# devboard_kw2xd_v2_0.net
KiCad netlist of a schematic drawn in EAGLE
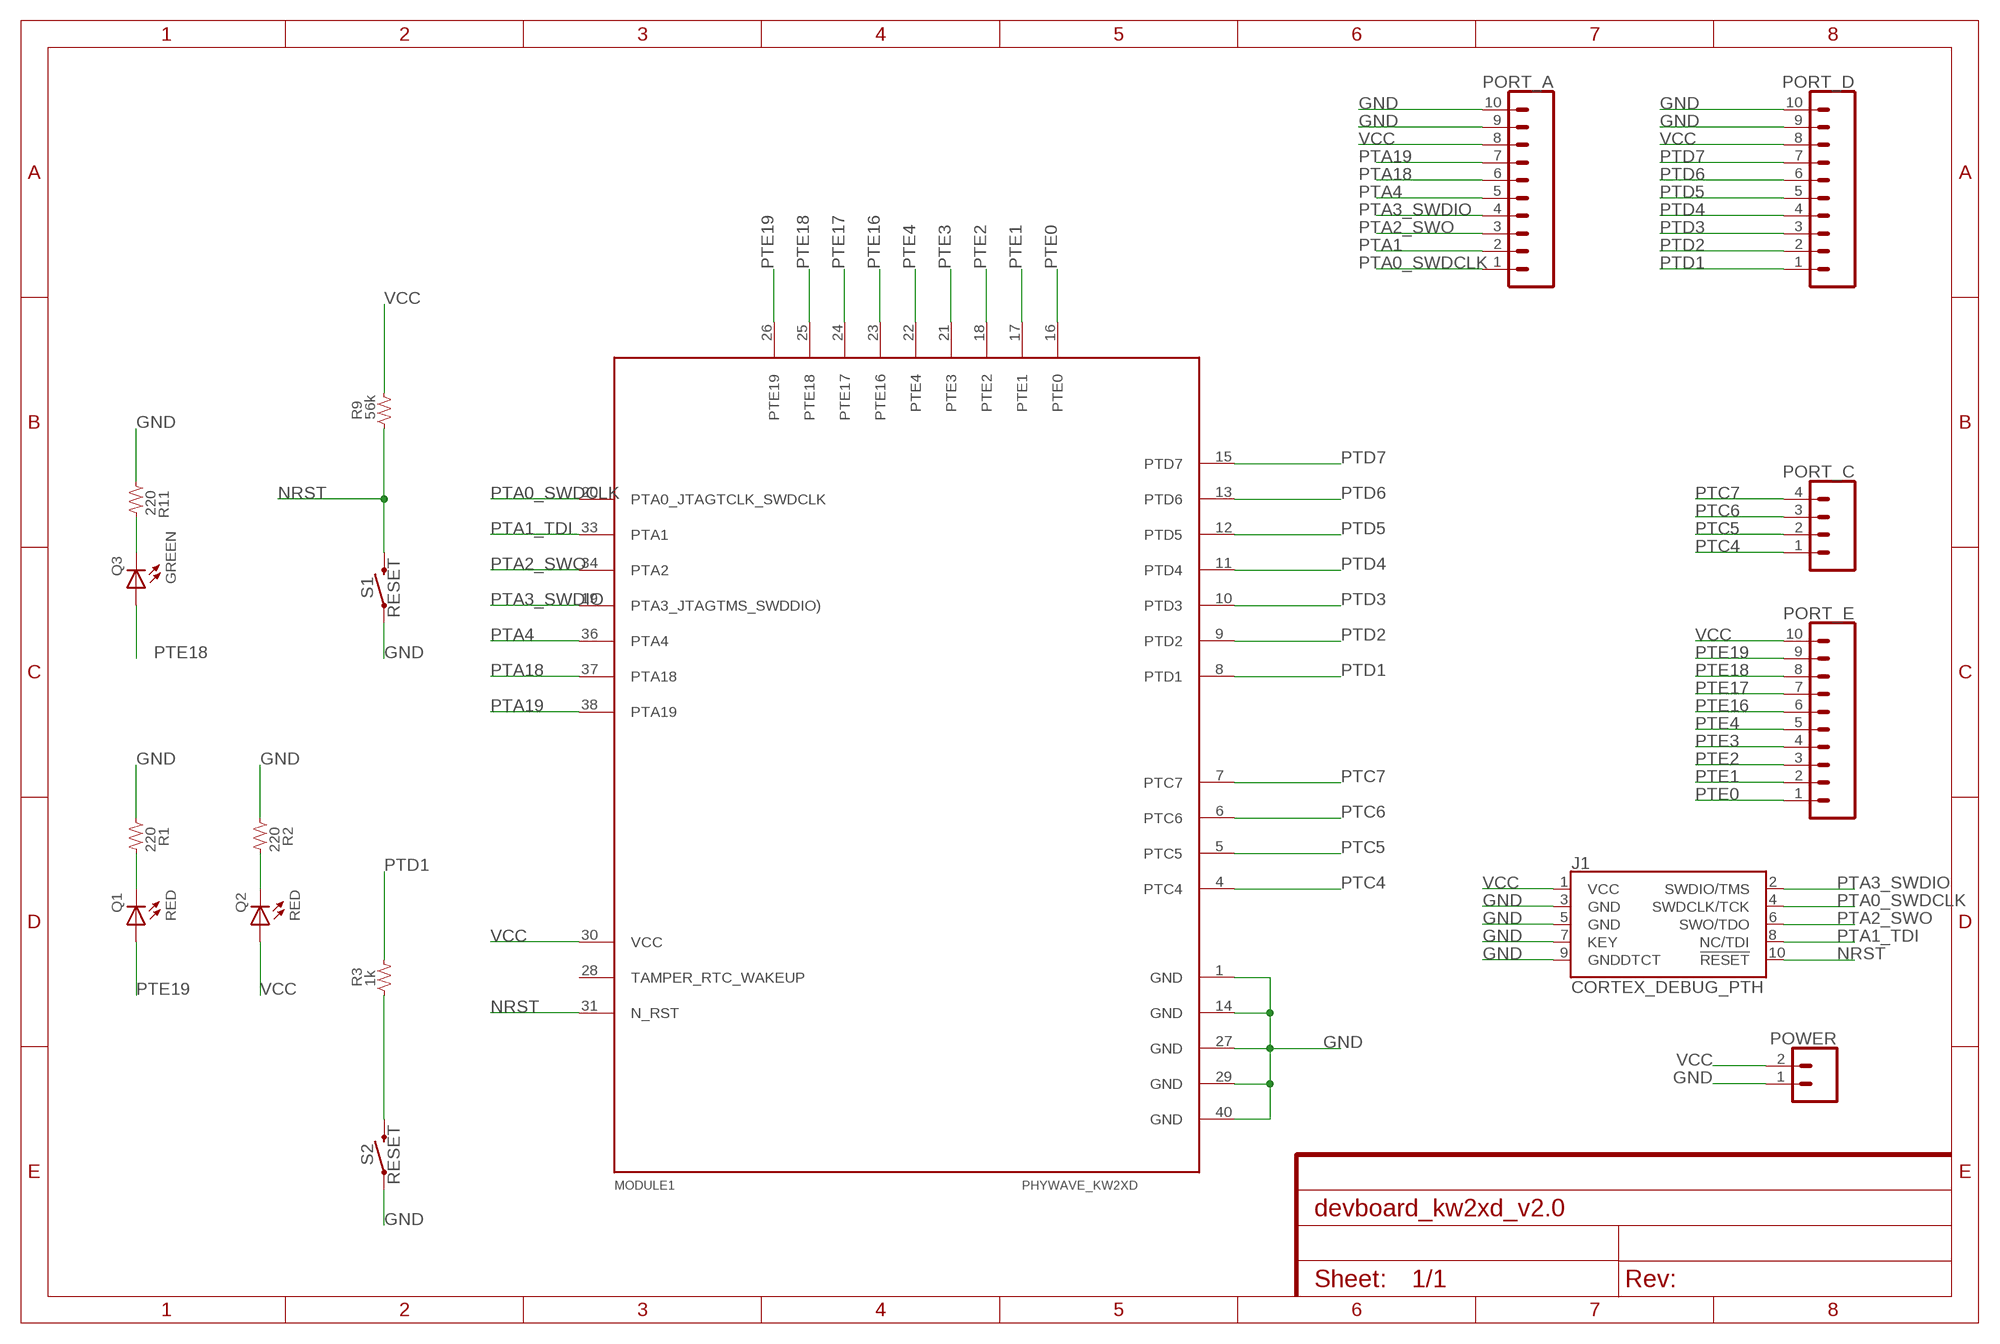
[diagram p0: schematic, sheet 1]

(export (version "E")
  (design (tool "Eeschema 10.0.6"))
  (components
    (comp (ref "J1")
      (value "CORTEX_DEBUG_PTH")
      (footprint "eagle-import:2X5-PTH-1.27MM")
      (libsource (lib "eagle-import") (part "CORTEX_DEBUG_PTH"))
    )
    (comp (ref "MODULE1")
      (value "PHYWAVE_KW2XD")
      (footprint "eagle-import:PHYWAVE_KW2XD")
      (libsource (lib "eagle-import") (part "PHYWAVE_KW2XD"))
    )
    (comp (ref "PORT_A")
      (value "CONN_10\"")
      (footprint "eagle-import:1X10")
      (libsource (lib "eagle-import") (part "CONN_10{dblquote}"))
    )
    (comp (ref "PORT_C")
      (value "CONN_04")
      (footprint "eagle-import:1X04")
      (libsource (lib "eagle-import") (part "CONN_04"))
    )
    (comp (ref "PORT_D")
      (value "CONN_10\"")
      (footprint "eagle-import:1X10")
      (libsource (lib "eagle-import") (part "CONN_10{dblquote}"))
    )
    (comp (ref "PORT_E")
      (value "CONN_10\"")
      (footprint "eagle-import:1X10")
      (libsource (lib "eagle-import") (part "CONN_10{dblquote}"))
    )
    (comp (ref "POWER")
      (value "CONN_02")
      (footprint "eagle-import:1X02")
      (libsource (lib "eagle-import") (part "CONN_02"))
    )
    (comp (ref "Q1")
      (value "RED")
      (footprint "eagle-import:LED0603")
      (libsource (lib "eagle-import") (part "LED-0603"))
    )
    (comp (ref "Q2")
      (value "RED")
      (footprint "eagle-import:LED0603")
      (libsource (lib "eagle-import") (part "LED-0603"))
    )
    (comp (ref "Q3")
      (value "GREEN")
      (footprint "eagle-import:LED0603")
      (libsource (lib "eagle-import") (part "LED-0603"))
    )
    (comp (ref "R1")
      (value "220")
      (footprint "eagle-import:SMD0603")
      (libsource (lib "eagle-import") (part "R-0603"))
    )
    (comp (ref "R2")
      (value "220")
      (footprint "eagle-import:SMD0603")
      (libsource (lib "eagle-import") (part "R-0603"))
    )
    (comp (ref "R3")
      (value "1k")
      (footprint "eagle-import:SMD0603")
      (libsource (lib "eagle-import") (part "R-0603"))
    )
    (comp (ref "R9")
      (value "56k")
      (footprint "eagle-import:SMD0603")
      (libsource (lib "eagle-import") (part "R-0603"))
    )
    (comp (ref "R11")
      (value "220")
      (footprint "eagle-import:SMD0603")
      (libsource (lib "eagle-import") (part "R-0603"))
    )
    (comp (ref "S1")
      (value "RESET")
      (footprint "eagle-import:TACTILE_SWITCH_SMD_4.6X2.8MM")
      (libsource (lib "eagle-import") (part "MOMENTARY-SWITCH-SPST-SMD-4.6X2.8MM"))
    )
    (comp (ref "S2")
      (value "RESET")
      (footprint "eagle-import:TACTILE_SWITCH_SMD_4.6X2.8MM")
      (libsource (lib "eagle-import") (part "MOMENTARY-SWITCH-SPST-SMD-4.6X2.8MM"))
    )
  )
  (nets
    (net (code "1") (name "/GND") (class "Default")
      (node (ref "J1") (pin "3") (pinfunction "GND_3") (pintype "bidirectional"))
      (node (ref "J1") (pin "5") (pinfunction "GND_5") (pintype "bidirectional"))
      (node (ref "J1") (pin "7") (pinfunction "KEY_7") (pintype "bidirectional"))
      (node (ref "J1") (pin "9") (pinfunction "GNDDTCT_9") (pintype "bidirectional"))
      (node (ref "MODULE1") (pin "1") (pinfunction "GND_1") (pintype "bidirectional"))
      (node (ref "MODULE1") (pin "14") (pinfunction "GND_14") (pintype "bidirectional"))
      (node (ref "MODULE1") (pin "27") (pinfunction "GND_27") (pintype "bidirectional"))
      (node (ref "MODULE1") (pin "29") (pinfunction "GND_29") (pintype "bidirectional"))
      (node (ref "MODULE1") (pin "40") (pinfunction "GND_40") (pintype "bidirectional"))
      (node (ref "PORT_A") (pin "10") (pinfunction "10_10") (pintype "passive"))
      (node (ref "PORT_A") (pin "9") (pinfunction "9_9") (pintype "passive"))
      (node (ref "PORT_D") (pin "10") (pinfunction "10_10") (pintype "passive"))
      (node (ref "PORT_D") (pin "9") (pinfunction "9_9") (pintype "passive"))
      (node (ref "POWER") (pin "1") (pinfunction "1_1") (pintype "passive"))
      (node (ref "R1") (pin "1") (pinfunction "1_1") (pintype "passive"))
      (node (ref "R11") (pin "1") (pinfunction "1_1") (pintype "passive"))
      (node (ref "R2") (pin "1") (pinfunction "1_1") (pintype "passive"))
      (node (ref "S1") (pin "1") (pinfunction "1_1") (pintype "passive"))
      (node (ref "S1") (pin "2") (pinfunction "1_2") (pintype "passive"))
      (node (ref "S2") (pin "1") (pinfunction "1_1") (pintype "passive"))
      (node (ref "S2") (pin "2") (pinfunction "1_2") (pintype "passive"))
    )
    (net (code "2") (name "/NRST") (class "Default")
      (node (ref "J1") (pin "10") (pinfunction "~{RESET}_10") (pintype "bidirectional"))
      (node (ref "MODULE1") (pin "31") (pinfunction "N_RST_31") (pintype "bidirectional"))
      (node (ref "R3") (pin "1") (pinfunction "1_1") (pintype "passive"))
      (node (ref "R9") (pin "1") (pinfunction "1_1") (pintype "passive"))
      (node (ref "S1") (pin "3") (pinfunction "2_3") (pintype "passive"))
      (node (ref "S1") (pin "4") (pinfunction "2_4") (pintype "passive"))
      (node (ref "S2") (pin "3") (pinfunction "2_3") (pintype "passive"))
      (node (ref "S2") (pin "4") (pinfunction "2_4") (pintype "passive"))
    )
    (net (code "3") (name "/PTA0_SWDCLK") (class "Default")
      (node (ref "J1") (pin "4") (pinfunction "SWDCLK/TCK_4") (pintype "bidirectional"))
      (node (ref "MODULE1") (pin "20") (pinfunction "PTA0_JTAGTCLK_SWDCLK_20") (pintype "bidirectional"))
      (node (ref "PORT_A") (pin "1") (pinfunction "1_1") (pintype "passive"))
    )
    (net (code "4") (name "/PTA1") (class "Default")
      (node (ref "PORT_A") (pin "2") (pinfunction "2_2") (pintype "passive"))
    )
    (net (code "5") (name "/PTA1_TDI") (class "Default")
      (node (ref "J1") (pin "8") (pinfunction "NC/TDI_8") (pintype "bidirectional"))
      (node (ref "MODULE1") (pin "33") (pinfunction "PTA1_33") (pintype "bidirectional"))
    )
    (net (code "6") (name "/PTA2_SWO") (class "Default")
      (node (ref "J1") (pin "6") (pinfunction "SWO/TDO_6") (pintype "bidirectional"))
      (node (ref "MODULE1") (pin "34") (pinfunction "PTA2_34") (pintype "bidirectional"))
      (node (ref "PORT_A") (pin "3") (pinfunction "3_3") (pintype "passive"))
    )
    (net (code "7") (name "/PTA3_SWDIO") (class "Default")
      (node (ref "J1") (pin "2") (pinfunction "SWDIO/TMS_2") (pintype "bidirectional"))
      (node (ref "MODULE1") (pin "19") (pinfunction "PTA3_JTAGTMS_SWDDIO)_19") (pintype "bidirectional"))
      (node (ref "PORT_A") (pin "4") (pinfunction "4_4") (pintype "passive"))
    )
    (net (code "8") (name "/PTA4") (class "Default")
      (node (ref "MODULE1") (pin "36") (pinfunction "PTA4_36") (pintype "bidirectional"))
      (node (ref "PORT_A") (pin "5") (pinfunction "5_5") (pintype "passive"))
    )
    (net (code "9") (name "/PTA18") (class "Default")
      (node (ref "MODULE1") (pin "37") (pinfunction "PTA18_37") (pintype "bidirectional"))
      (node (ref "PORT_A") (pin "6") (pinfunction "6_6") (pintype "passive"))
    )
    (net (code "10") (name "/PTA19") (class "Default")
      (node (ref "MODULE1") (pin "38") (pinfunction "PTA19_38") (pintype "bidirectional"))
      (node (ref "PORT_A") (pin "7") (pinfunction "7_7") (pintype "passive"))
    )
    (net (code "11") (name "/PTC4") (class "Default")
      (node (ref "MODULE1") (pin "4") (pinfunction "PTC4_4") (pintype "bidirectional"))
      (node (ref "PORT_C") (pin "1") (pinfunction "1_1") (pintype "passive"))
    )
    (net (code "12") (name "/PTC5") (class "Default")
      (node (ref "MODULE1") (pin "5") (pinfunction "PTC5_5") (pintype "bidirectional"))
      (node (ref "PORT_C") (pin "2") (pinfunction "2_2") (pintype "passive"))
    )
    (net (code "13") (name "/PTC6") (class "Default")
      (node (ref "MODULE1") (pin "6") (pinfunction "PTC6_6") (pintype "bidirectional"))
      (node (ref "PORT_C") (pin "3") (pinfunction "3_3") (pintype "passive"))
    )
    (net (code "14") (name "/PTC7") (class "Default")
      (node (ref "MODULE1") (pin "7") (pinfunction "PTC7_7") (pintype "bidirectional"))
      (node (ref "PORT_C") (pin "4") (pinfunction "4_4") (pintype "passive"))
    )
    (net (code "15") (name "/PTD1") (class "Default")
      (node (ref "MODULE1") (pin "8") (pinfunction "PTD1_8") (pintype "bidirectional"))
      (node (ref "PORT_D") (pin "1") (pinfunction "1_1") (pintype "passive"))
      (node (ref "R3") (pin "2") (pinfunction "2_2") (pintype "passive"))
    )
    (net (code "16") (name "/PTD2") (class "Default")
      (node (ref "MODULE1") (pin "9") (pinfunction "PTD2_9") (pintype "bidirectional"))
      (node (ref "PORT_D") (pin "2") (pinfunction "2_2") (pintype "passive"))
    )
    (net (code "17") (name "/PTD3") (class "Default")
      (node (ref "MODULE1") (pin "10") (pinfunction "PTD3_10") (pintype "bidirectional"))
      (node (ref "PORT_D") (pin "3") (pinfunction "3_3") (pintype "passive"))
    )
    (net (code "18") (name "/PTD4") (class "Default")
      (node (ref "MODULE1") (pin "11") (pinfunction "PTD4_11") (pintype "bidirectional"))
      (node (ref "PORT_D") (pin "4") (pinfunction "4_4") (pintype "passive"))
    )
    (net (code "19") (name "/PTD5") (class "Default")
      (node (ref "MODULE1") (pin "12") (pinfunction "PTD5_12") (pintype "bidirectional"))
      (node (ref "PORT_D") (pin "5") (pinfunction "5_5") (pintype "passive"))
    )
    (net (code "20") (name "/PTD6") (class "Default")
      (node (ref "MODULE1") (pin "13") (pinfunction "PTD6_13") (pintype "bidirectional"))
      (node (ref "PORT_D") (pin "6") (pinfunction "6_6") (pintype "passive"))
    )
    (net (code "21") (name "/PTD7") (class "Default")
      (node (ref "MODULE1") (pin "15") (pinfunction "PTD7_15") (pintype "bidirectional"))
      (node (ref "PORT_D") (pin "7") (pinfunction "7_7") (pintype "passive"))
    )
    (net (code "22") (name "/PTE0") (class "Default")
      (node (ref "MODULE1") (pin "16") (pinfunction "PTE0_16") (pintype "bidirectional"))
      (node (ref "PORT_E") (pin "1") (pinfunction "1_1") (pintype "passive"))
    )
    (net (code "23") (name "/PTE1") (class "Default")
      (node (ref "MODULE1") (pin "17") (pinfunction "PTE1_17") (pintype "bidirectional"))
      (node (ref "PORT_E") (pin "2") (pinfunction "2_2") (pintype "passive"))
    )
    (net (code "24") (name "/PTE2") (class "Default")
      (node (ref "MODULE1") (pin "18") (pinfunction "PTE2_18") (pintype "bidirectional"))
      (node (ref "PORT_E") (pin "3") (pinfunction "3_3") (pintype "passive"))
    )
    (net (code "25") (name "/PTE3") (class "Default")
      (node (ref "MODULE1") (pin "21") (pinfunction "PTE3_21") (pintype "bidirectional"))
      (node (ref "PORT_E") (pin "4") (pinfunction "4_4") (pintype "passive"))
    )
    (net (code "26") (name "/PTE4") (class "Default")
      (node (ref "MODULE1") (pin "22") (pinfunction "PTE4_22") (pintype "bidirectional"))
      (node (ref "PORT_E") (pin "5") (pinfunction "5_5") (pintype "passive"))
    )
    (net (code "27") (name "/PTE16") (class "Default")
      (node (ref "MODULE1") (pin "23") (pinfunction "PTE16_23") (pintype "bidirectional"))
      (node (ref "PORT_E") (pin "6") (pinfunction "6_6") (pintype "passive"))
    )
    (net (code "28") (name "/PTE17") (class "Default")
      (node (ref "MODULE1") (pin "24") (pinfunction "PTE17_24") (pintype "bidirectional"))
      (node (ref "PORT_E") (pin "7") (pinfunction "7_7") (pintype "passive"))
    )
    (net (code "29") (name "/PTE18") (class "Default")
      (node (ref "MODULE1") (pin "25") (pinfunction "PTE18_25") (pintype "bidirectional"))
      (node (ref "PORT_E") (pin "8") (pinfunction "8_8") (pintype "passive"))
      (node (ref "Q3") (pin "A") (pinfunction "A_A") (pintype "passive"))
    )
    (net (code "30") (name "/PTE19") (class "Default")
      (node (ref "MODULE1") (pin "26") (pinfunction "PTE19_26") (pintype "bidirectional"))
      (node (ref "PORT_E") (pin "9") (pinfunction "9_9") (pintype "passive"))
      (node (ref "Q1") (pin "A") (pinfunction "A_A") (pintype "passive"))
    )
    (net (code "31") (name "/VCC") (class "Default")
      (node (ref "J1") (pin "1") (pinfunction "VCC_1") (pintype "bidirectional"))
      (node (ref "MODULE1") (pin "30") (pinfunction "VCC_30") (pintype "bidirectional"))
      (node (ref "PORT_A") (pin "8") (pinfunction "8_8") (pintype "passive"))
      (node (ref "PORT_D") (pin "8") (pinfunction "8_8") (pintype "passive"))
      (node (ref "PORT_E") (pin "10") (pinfunction "10_10") (pintype "passive"))
      (node (ref "POWER") (pin "2") (pinfunction "2_2") (pintype "passive"))
      (node (ref "Q2") (pin "A") (pinfunction "A_A") (pintype "passive"))
      (node (ref "R9") (pin "2") (pinfunction "2_2") (pintype "passive"))
    )
    (net (code "32") (name "Net-(Q1-PadC)") (class "Default")
      (node (ref "Q1") (pin "C") (pinfunction "C_C") (pintype "passive"))
      (node (ref "R1") (pin "2") (pinfunction "2_2") (pintype "passive"))
    )
    (net (code "33") (name "Net-(Q2-PadC)") (class "Default")
      (node (ref "Q2") (pin "C") (pinfunction "C_C") (pintype "passive"))
      (node (ref "R2") (pin "2") (pinfunction "2_2") (pintype "passive"))
    )
    (net (code "34") (name "Net-(Q3-PadC)") (class "Default")
      (node (ref "Q3") (pin "C") (pinfunction "C_C") (pintype "passive"))
      (node (ref "R11") (pin "2") (pinfunction "2_2") (pintype "passive"))
    )
    (net (code "35") (name "unconnected-(MODULE1-TAMPER_RTC_WAKEUP-Pad28)") (class "Default")
      (node (ref "MODULE1") (pin "28") (pinfunction "TAMPER_RTC_WAKEUP_28") (pintype "bidirectional"))
    )
  )
)
